# peizo_board_PLA.net
KiCad netlist of a schematic drawn in EAGLE
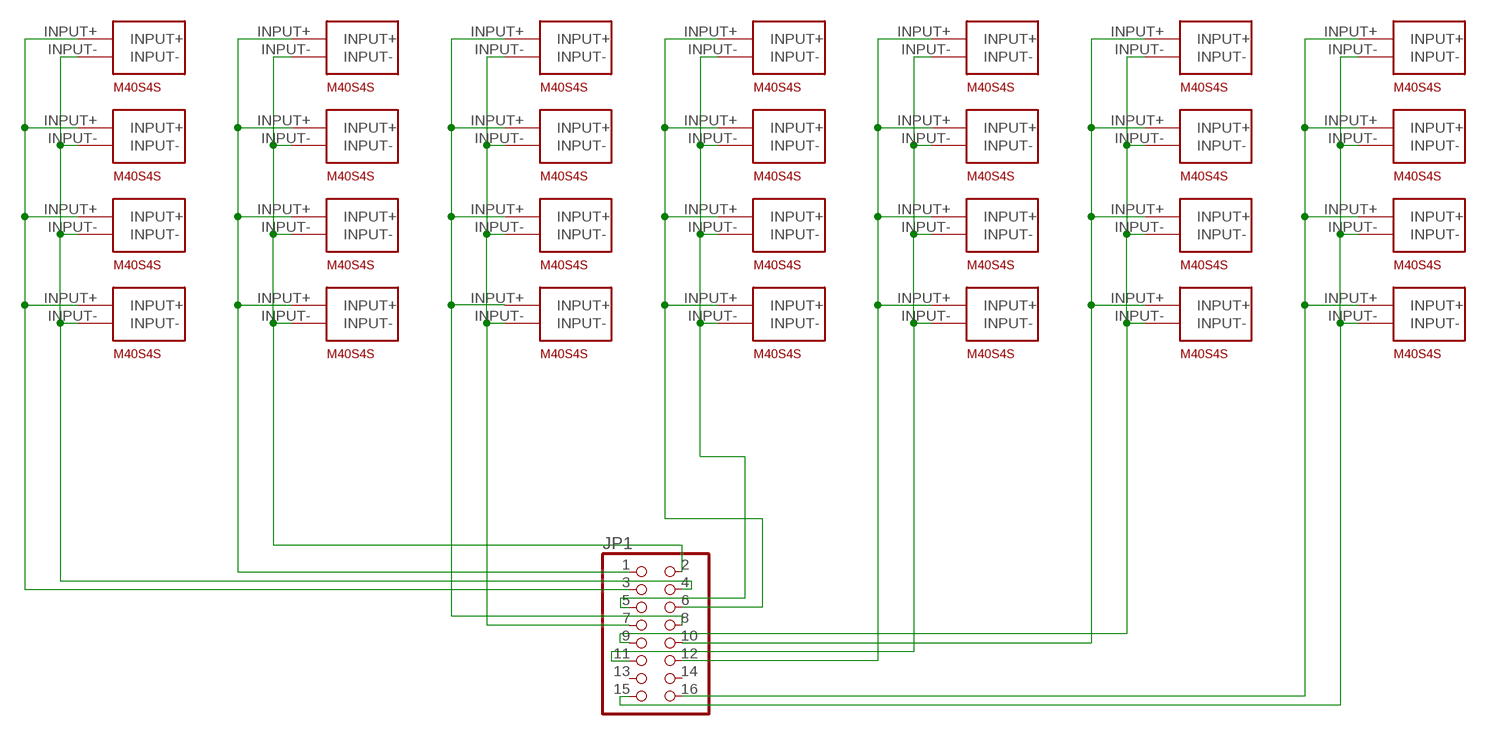
[diagram p0: schematic, sheet 1]

(export (version "E")
  (design (tool "Eeschema 10.0.6"))
  (components
    (comp (ref "JP1")
      (value "PINHD-2X8")
      (footprint "eagle-import:2X08")
      (libsource (lib "eagle-import") (part "PINHD-2X8"))
    )
    (comp (ref "U$1")
      (value "MA40S4S")
      (footprint "eagle-import:MA40S4S")
      (libsource (lib "eagle-import") (part "MA40S4S"))
    )
    (comp (ref "U$2")
      (value "MA40S4S")
      (footprint "eagle-import:MA40S4S")
      (libsource (lib "eagle-import") (part "MA40S4S"))
    )
    (comp (ref "U$3")
      (value "MA40S4S")
      (footprint "eagle-import:MA40S4S")
      (libsource (lib "eagle-import") (part "MA40S4S"))
    )
    (comp (ref "U$4")
      (value "MA40S4S")
      (footprint "eagle-import:MA40S4S")
      (libsource (lib "eagle-import") (part "MA40S4S"))
    )
    (comp (ref "U$5")
      (value "MA40S4S")
      (footprint "eagle-import:MA40S4S")
      (libsource (lib "eagle-import") (part "MA40S4S"))
    )
    (comp (ref "U$6")
      (value "MA40S4S")
      (footprint "eagle-import:MA40S4S")
      (libsource (lib "eagle-import") (part "MA40S4S"))
    )
    (comp (ref "U$7")
      (value "MA40S4S")
      (footprint "eagle-import:MA40S4S")
      (libsource (lib "eagle-import") (part "MA40S4S"))
    )
    (comp (ref "U$8")
      (value "MA40S4S")
      (footprint "eagle-import:MA40S4S")
      (libsource (lib "eagle-import") (part "MA40S4S"))
    )
    (comp (ref "U$9")
      (value "MA40S4S")
      (footprint "eagle-import:MA40S4S")
      (libsource (lib "eagle-import") (part "MA40S4S"))
    )
    (comp (ref "U$10")
      (value "MA40S4S")
      (footprint "eagle-import:MA40S4S")
      (libsource (lib "eagle-import") (part "MA40S4S"))
    )
    (comp (ref "U$11")
      (value "MA40S4S")
      (footprint "eagle-import:MA40S4S")
      (libsource (lib "eagle-import") (part "MA40S4S"))
    )
    (comp (ref "U$12")
      (value "MA40S4S")
      (footprint "eagle-import:MA40S4S")
      (libsource (lib "eagle-import") (part "MA40S4S"))
    )
    (comp (ref "U$13")
      (value "MA40S4S")
      (footprint "eagle-import:MA40S4S")
      (libsource (lib "eagle-import") (part "MA40S4S"))
    )
    (comp (ref "U$14")
      (value "MA40S4S")
      (footprint "eagle-import:MA40S4S")
      (libsource (lib "eagle-import") (part "MA40S4S"))
    )
    (comp (ref "U$15")
      (value "MA40S4S")
      (footprint "eagle-import:MA40S4S")
      (libsource (lib "eagle-import") (part "MA40S4S"))
    )
    (comp (ref "U$16")
      (value "MA40S4S")
      (footprint "eagle-import:MA40S4S")
      (libsource (lib "eagle-import") (part "MA40S4S"))
    )
    (comp (ref "U$17")
      (value "MA40S4S")
      (footprint "eagle-import:MA40S4S")
      (libsource (lib "eagle-import") (part "MA40S4S"))
    )
    (comp (ref "U$18")
      (value "MA40S4S")
      (footprint "eagle-import:MA40S4S")
      (libsource (lib "eagle-import") (part "MA40S4S"))
    )
    (comp (ref "U$19")
      (value "MA40S4S")
      (footprint "eagle-import:MA40S4S")
      (libsource (lib "eagle-import") (part "MA40S4S"))
    )
    (comp (ref "U$20")
      (value "MA40S4S")
      (footprint "eagle-import:MA40S4S")
      (libsource (lib "eagle-import") (part "MA40S4S"))
    )
    (comp (ref "U$21")
      (value "MA40S4S")
      (footprint "eagle-import:MA40S4S")
      (libsource (lib "eagle-import") (part "MA40S4S"))
    )
    (comp (ref "U$22")
      (value "MA40S4S")
      (footprint "eagle-import:MA40S4S")
      (libsource (lib "eagle-import") (part "MA40S4S"))
    )
    (comp (ref "U$23")
      (value "MA40S4S")
      (footprint "eagle-import:MA40S4S")
      (libsource (lib "eagle-import") (part "MA40S4S"))
    )
    (comp (ref "U$24")
      (value "MA40S4S")
      (footprint "eagle-import:MA40S4S")
      (libsource (lib "eagle-import") (part "MA40S4S"))
    )
    (comp (ref "U$25")
      (value "MA40S4S")
      (footprint "eagle-import:MA40S4S")
      (libsource (lib "eagle-import") (part "MA40S4S"))
    )
    (comp (ref "U$26")
      (value "MA40S4S")
      (footprint "eagle-import:MA40S4S")
      (libsource (lib "eagle-import") (part "MA40S4S"))
    )
    (comp (ref "U$27")
      (value "MA40S4S")
      (footprint "eagle-import:MA40S4S")
      (libsource (lib "eagle-import") (part "MA40S4S"))
    )
    (comp (ref "U$28")
      (value "MA40S4S")
      (footprint "eagle-import:MA40S4S")
      (libsource (lib "eagle-import") (part "MA40S4S"))
    )
  )
  (nets
    (net (code "1") (name "Net-(JP1-Pad1)") (class "Default")
      (node (ref "JP1") (pin "1") (pinfunction "1_1") (pintype "passive"))
      (node (ref "U$5") (pin "INPUT+") (pinfunction "INPUT+_INPUT+") (pintype "bidirectional"))
      (node (ref "U$6") (pin "INPUT+") (pinfunction "INPUT+_INPUT+") (pintype "bidirectional"))
      (node (ref "U$7") (pin "INPUT+") (pinfunction "INPUT+_INPUT+") (pintype "bidirectional"))
      (node (ref "U$8") (pin "INPUT+") (pinfunction "INPUT+_INPUT+") (pintype "bidirectional"))
    )
    (net (code "2") (name "Net-(JP1-Pad2)") (class "Default")
      (node (ref "JP1") (pin "2") (pinfunction "2_2") (pintype "passive"))
      (node (ref "U$5") (pin "INPUT-") (pinfunction "INPUT-_INPUT-") (pintype "bidirectional"))
      (node (ref "U$6") (pin "INPUT-") (pinfunction "INPUT-_INPUT-") (pintype "bidirectional"))
      (node (ref "U$7") (pin "INPUT-") (pinfunction "INPUT-_INPUT-") (pintype "bidirectional"))
      (node (ref "U$8") (pin "INPUT-") (pinfunction "INPUT-_INPUT-") (pintype "bidirectional"))
    )
    (net (code "3") (name "Net-(JP1-Pad3)") (class "Default")
      (node (ref "JP1") (pin "3") (pinfunction "3_3") (pintype "passive"))
      (node (ref "U$1") (pin "INPUT+") (pinfunction "INPUT+_INPUT+") (pintype "bidirectional"))
      (node (ref "U$2") (pin "INPUT+") (pinfunction "INPUT+_INPUT+") (pintype "bidirectional"))
      (node (ref "U$3") (pin "INPUT+") (pinfunction "INPUT+_INPUT+") (pintype "bidirectional"))
      (node (ref "U$4") (pin "INPUT+") (pinfunction "INPUT+_INPUT+") (pintype "bidirectional"))
    )
    (net (code "4") (name "Net-(JP1-Pad4)") (class "Default")
      (node (ref "JP1") (pin "4") (pinfunction "4_4") (pintype "passive"))
      (node (ref "U$1") (pin "INPUT-") (pinfunction "INPUT-_INPUT-") (pintype "bidirectional"))
      (node (ref "U$2") (pin "INPUT-") (pinfunction "INPUT-_INPUT-") (pintype "bidirectional"))
      (node (ref "U$3") (pin "INPUT-") (pinfunction "INPUT-_INPUT-") (pintype "bidirectional"))
      (node (ref "U$4") (pin "INPUT-") (pinfunction "INPUT-_INPUT-") (pintype "bidirectional"))
    )
    (net (code "5") (name "Net-(JP1-Pad5)") (class "Default")
      (node (ref "JP1") (pin "5") (pinfunction "5_5") (pintype "passive"))
      (node (ref "U$13") (pin "INPUT-") (pinfunction "INPUT-_INPUT-") (pintype "bidirectional"))
      (node (ref "U$14") (pin "INPUT-") (pinfunction "INPUT-_INPUT-") (pintype "bidirectional"))
      (node (ref "U$15") (pin "INPUT-") (pinfunction "INPUT-_INPUT-") (pintype "bidirectional"))
      (node (ref "U$16") (pin "INPUT-") (pinfunction "INPUT-_INPUT-") (pintype "bidirectional"))
    )
    (net (code "6") (name "Net-(JP1-Pad6)") (class "Default")
      (node (ref "JP1") (pin "6") (pinfunction "6_6") (pintype "passive"))
      (node (ref "U$13") (pin "INPUT+") (pinfunction "INPUT+_INPUT+") (pintype "bidirectional"))
      (node (ref "U$14") (pin "INPUT+") (pinfunction "INPUT+_INPUT+") (pintype "bidirectional"))
      (node (ref "U$15") (pin "INPUT+") (pinfunction "INPUT+_INPUT+") (pintype "bidirectional"))
      (node (ref "U$16") (pin "INPUT+") (pinfunction "INPUT+_INPUT+") (pintype "bidirectional"))
    )
    (net (code "7") (name "Net-(JP1-Pad7)") (class "Default")
      (node (ref "JP1") (pin "7") (pinfunction "7_7") (pintype "passive"))
      (node (ref "U$10") (pin "INPUT-") (pinfunction "INPUT-_INPUT-") (pintype "bidirectional"))
      (node (ref "U$11") (pin "INPUT-") (pinfunction "INPUT-_INPUT-") (pintype "bidirectional"))
      (node (ref "U$12") (pin "INPUT-") (pinfunction "INPUT-_INPUT-") (pintype "bidirectional"))
      (node (ref "U$9") (pin "INPUT-") (pinfunction "INPUT-_INPUT-") (pintype "bidirectional"))
    )
    (net (code "8") (name "Net-(JP1-Pad8)") (class "Default")
      (node (ref "JP1") (pin "8") (pinfunction "8_8") (pintype "passive"))
      (node (ref "U$10") (pin "INPUT+") (pinfunction "INPUT+_INPUT+") (pintype "bidirectional"))
      (node (ref "U$11") (pin "INPUT+") (pinfunction "INPUT+_INPUT+") (pintype "bidirectional"))
      (node (ref "U$12") (pin "INPUT+") (pinfunction "INPUT+_INPUT+") (pintype "bidirectional"))
      (node (ref "U$9") (pin "INPUT+") (pinfunction "INPUT+_INPUT+") (pintype "bidirectional"))
    )
    (net (code "9") (name "Net-(JP1-Pad9)") (class "Default")
      (node (ref "JP1") (pin "9") (pinfunction "9_9") (pintype "passive"))
      (node (ref "U$21") (pin "INPUT-") (pinfunction "INPUT-_INPUT-") (pintype "bidirectional"))
      (node (ref "U$22") (pin "INPUT-") (pinfunction "INPUT-_INPUT-") (pintype "bidirectional"))
      (node (ref "U$23") (pin "INPUT-") (pinfunction "INPUT-_INPUT-") (pintype "bidirectional"))
      (node (ref "U$24") (pin "INPUT-") (pinfunction "INPUT-_INPUT-") (pintype "bidirectional"))
    )
    (net (code "10") (name "Net-(JP1-Pad10)") (class "Default")
      (node (ref "JP1") (pin "10") (pinfunction "10_10") (pintype "passive"))
      (node (ref "U$21") (pin "INPUT+") (pinfunction "INPUT+_INPUT+") (pintype "bidirectional"))
      (node (ref "U$22") (pin "INPUT+") (pinfunction "INPUT+_INPUT+") (pintype "bidirectional"))
      (node (ref "U$23") (pin "INPUT+") (pinfunction "INPUT+_INPUT+") (pintype "bidirectional"))
      (node (ref "U$24") (pin "INPUT+") (pinfunction "INPUT+_INPUT+") (pintype "bidirectional"))
    )
    (net (code "11") (name "Net-(JP1-Pad11)") (class "Default")
      (node (ref "JP1") (pin "11") (pinfunction "11_11") (pintype "passive"))
      (node (ref "U$17") (pin "INPUT-") (pinfunction "INPUT-_INPUT-") (pintype "bidirectional"))
      (node (ref "U$18") (pin "INPUT-") (pinfunction "INPUT-_INPUT-") (pintype "bidirectional"))
      (node (ref "U$19") (pin "INPUT-") (pinfunction "INPUT-_INPUT-") (pintype "bidirectional"))
      (node (ref "U$20") (pin "INPUT-") (pinfunction "INPUT-_INPUT-") (pintype "bidirectional"))
    )
    (net (code "12") (name "Net-(JP1-Pad12)") (class "Default")
      (node (ref "JP1") (pin "12") (pinfunction "12_12") (pintype "passive"))
      (node (ref "U$17") (pin "INPUT+") (pinfunction "INPUT+_INPUT+") (pintype "bidirectional"))
      (node (ref "U$18") (pin "INPUT+") (pinfunction "INPUT+_INPUT+") (pintype "bidirectional"))
      (node (ref "U$19") (pin "INPUT+") (pinfunction "INPUT+_INPUT+") (pintype "bidirectional"))
      (node (ref "U$20") (pin "INPUT+") (pinfunction "INPUT+_INPUT+") (pintype "bidirectional"))
    )
    (net (code "13") (name "Net-(JP1-Pad15)") (class "Default")
      (node (ref "JP1") (pin "15") (pinfunction "15_15") (pintype "passive"))
      (node (ref "U$25") (pin "INPUT-") (pinfunction "INPUT-_INPUT-") (pintype "bidirectional"))
      (node (ref "U$26") (pin "INPUT-") (pinfunction "INPUT-_INPUT-") (pintype "bidirectional"))
      (node (ref "U$27") (pin "INPUT-") (pinfunction "INPUT-_INPUT-") (pintype "bidirectional"))
      (node (ref "U$28") (pin "INPUT-") (pinfunction "INPUT-_INPUT-") (pintype "bidirectional"))
    )
    (net (code "14") (name "Net-(JP1-Pad16)") (class "Default")
      (node (ref "JP1") (pin "16") (pinfunction "16_16") (pintype "passive"))
      (node (ref "U$25") (pin "INPUT+") (pinfunction "INPUT+_INPUT+") (pintype "bidirectional"))
      (node (ref "U$26") (pin "INPUT+") (pinfunction "INPUT+_INPUT+") (pintype "bidirectional"))
      (node (ref "U$27") (pin "INPUT+") (pinfunction "INPUT+_INPUT+") (pintype "bidirectional"))
      (node (ref "U$28") (pin "INPUT+") (pinfunction "INPUT+_INPUT+") (pintype "bidirectional"))
    )
    (net (code "15") (name "unconnected-(JP1-Pad13)") (class "Default")
      (node (ref "JP1") (pin "13") (pinfunction "13_13") (pintype "passive"))
    )
    (net (code "16") (name "unconnected-(JP1-Pad14)") (class "Default")
      (node (ref "JP1") (pin "14") (pinfunction "14_14") (pintype "passive"))
    )
  )
)
